# BrainA2-B-11Nov2014.net
KiCad netlist of a schematic drawn in EAGLE
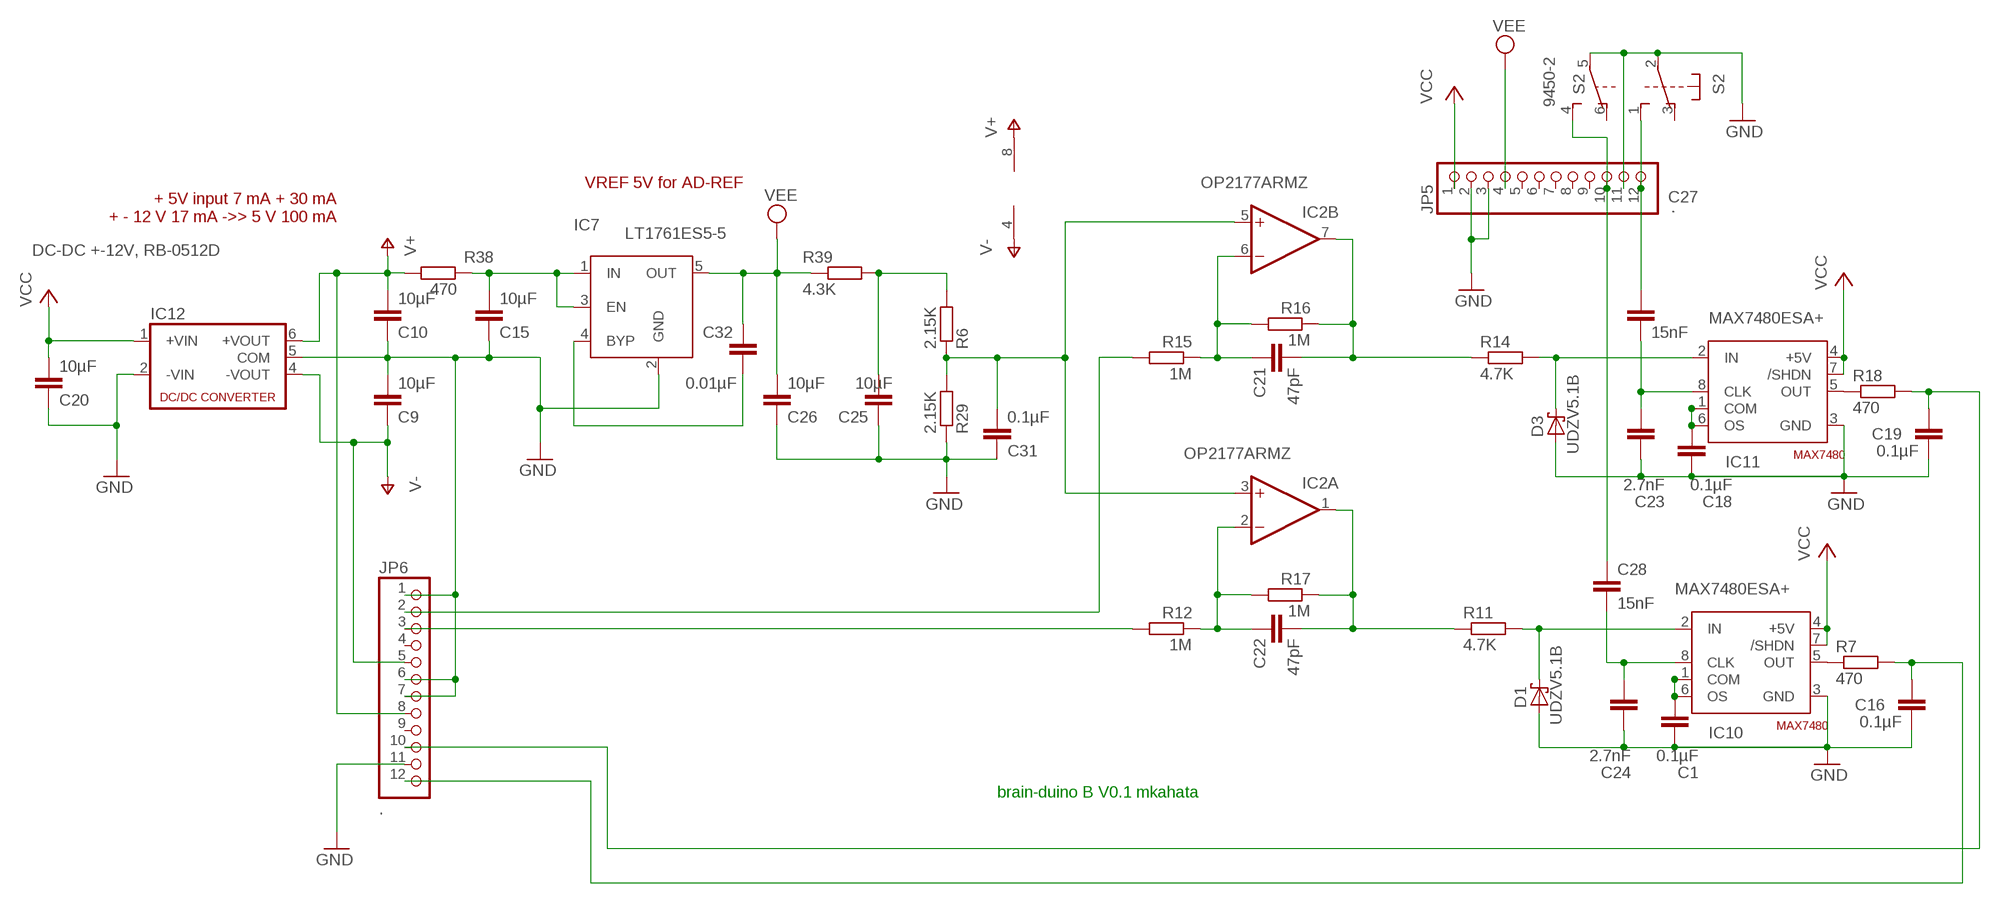
[diagram p0: schematic, sheet 1]

(export (version "E")
  (design (tool "Eeschema 10.0.6"))
  (components
    (comp (ref "C1")
      (value "0.1µF")
      (footprint "eagle-import:C0603")
      (libsource (lib "eagle-import") (part "C-EUC0603"))
    )
    (comp (ref "C9")
      (value "10µF")
      (footprint "eagle-import:C0603")
      (libsource (lib "eagle-import") (part "C-EUC0603"))
    )
    (comp (ref "C10")
      (value "10µF")
      (footprint "eagle-import:C0603")
      (libsource (lib "eagle-import") (part "C-EUC0603"))
    )
    (comp (ref "C15")
      (value "10µF")
      (footprint "eagle-import:C0603")
      (libsource (lib "eagle-import") (part "C-EUC0603"))
    )
    (comp (ref "C16")
      (value "0.1µF")
      (footprint "eagle-import:C0603")
      (libsource (lib "eagle-import") (part "C-EUC0603"))
    )
    (comp (ref "C18")
      (value "0.1µF")
      (footprint "eagle-import:C0603")
      (libsource (lib "eagle-import") (part "C-EUC0603"))
    )
    (comp (ref "C19")
      (value "0.1µF")
      (footprint "eagle-import:C0603")
      (libsource (lib "eagle-import") (part "C-EUC0603"))
    )
    (comp (ref "C20")
      (value "10µF")
      (footprint "eagle-import:C0603")
      (libsource (lib "eagle-import") (part "C-EUC0603"))
    )
    (comp (ref "C21")
      (value "47pF")
      (footprint "eagle-import:C0603")
      (libsource (lib "eagle-import") (part "C-EUC0603"))
    )
    (comp (ref "C22")
      (value "47pF")
      (footprint "eagle-import:C0603")
      (libsource (lib "eagle-import") (part "C-EUC0603"))
    )
    (comp (ref "C23")
      (value "2.7nF")
      (footprint "eagle-import:C0603")
      (libsource (lib "eagle-import") (part "C-EUC0603"))
    )
    (comp (ref "C24")
      (value "2.7nF")
      (footprint "eagle-import:C0603")
      (libsource (lib "eagle-import") (part "C-EUC0603"))
    )
    (comp (ref "C25")
      (value "10µF")
      (footprint "eagle-import:C0603")
      (libsource (lib "eagle-import") (part "C-EUC0603"))
    )
    (comp (ref "C26")
      (value "10µF")
      (footprint "eagle-import:C0603")
      (libsource (lib "eagle-import") (part "C-EUC0603"))
    )
    (comp (ref "C27")
      (value "15nF")
      (footprint "eagle-import:C0603")
      (libsource (lib "eagle-import") (part "C-EUC0603"))
    )
    (comp (ref "C28")
      (value "15nF")
      (footprint "eagle-import:C0603")
      (libsource (lib "eagle-import") (part "C-EUC0603"))
    )
    (comp (ref "C31")
      (value "0.1µF")
      (footprint "eagle-import:C0603")
      (libsource (lib "eagle-import") (part "C-EUC0603"))
    )
    (comp (ref "C32")
      (value "0.01µF")
      (footprint "eagle-import:C0603")
      (libsource (lib "eagle-import") (part "C-EUC0603"))
    )
    (comp (ref "D1")
      (value "UDZV5.1B")
      (footprint "eagle-import:SOD323_ST")
      (libsource (lib "eagle-import") (part "BAT60J"))
    )
    (comp (ref "D3")
      (value "UDZV5.1B")
      (footprint "eagle-import:SOD323_ST")
      (libsource (lib "eagle-import") (part "BAT60J"))
    )
    (comp (ref "IC2")
      (value "OP2177ARMZ")
      (footprint "eagle-import:MSOP08")
      (libsource (lib "eagle-import") (part "OP1277RM"))
    )
    (comp (ref "IC7")
      (value "LT1761ES5-5")
      (footprint "eagle-import:SOT23-5")
      (libsource (lib "eagle-import") (part "MIC5219XX"))
    )
    (comp (ref "IC10")
      (value "MAX7480ESA+")
      (footprint "eagle-import:MAX7480")
      (libsource (lib "eagle-import") (part "MAX7480"))
    )
    (comp (ref "IC11")
      (value "MAX7480ESA+")
      (footprint "eagle-import:MAX7480")
      (libsource (lib "eagle-import") (part "MAX7480"))
    )
    (comp (ref "IC12")
      (value "DC-DC +-12V, RB-0512D")
      (footprint "eagle-import:RB-0515D")
      (libsource (lib "eagle-import") (part "RB-0515D"))
    )
    (comp (ref "JP5")
      (value ".")
      (footprint "eagle-import:1X12")
      (libsource (lib "eagle-import") (part "PINHD-1X12"))
    )
    (comp (ref "JP6")
      (value ".")
      (footprint "eagle-import:1X12")
      (libsource (lib "eagle-import") (part "PINHD-1X12"))
    )
    (comp (ref "R6")
      (value "2.15K")
      (footprint "eagle-import:R0603")
      (libsource (lib "eagle-import") (part "R-EU_R0603"))
    )
    (comp (ref "R7")
      (value "470")
      (footprint "eagle-import:R0603")
      (libsource (lib "eagle-import") (part "R-EU_R0603"))
    )
    (comp (ref "R11")
      (value "4.7K")
      (footprint "eagle-import:R0603")
      (libsource (lib "eagle-import") (part "R-EU_R0603"))
    )
    (comp (ref "R12")
      (value "1M")
      (footprint "eagle-import:R0603")
      (libsource (lib "eagle-import") (part "R-EU_R0603"))
    )
    (comp (ref "R14")
      (value "4.7K")
      (footprint "eagle-import:R0603")
      (libsource (lib "eagle-import") (part "R-EU_R0603"))
    )
    (comp (ref "R15")
      (value "1M")
      (footprint "eagle-import:R0603")
      (libsource (lib "eagle-import") (part "R-EU_R0603"))
    )
    (comp (ref "R16")
      (value "1M")
      (footprint "eagle-import:R0603")
      (libsource (lib "eagle-import") (part "R-EU_R0603"))
    )
    (comp (ref "R17")
      (value "1M")
      (footprint "eagle-import:R0603")
      (libsource (lib "eagle-import") (part "R-EU_R0603"))
    )
    (comp (ref "R18")
      (value "470")
      (footprint "eagle-import:R0603")
      (libsource (lib "eagle-import") (part "R-EU_R0603"))
    )
    (comp (ref "R29")
      (value "2.15K")
      (footprint "eagle-import:R0603")
      (libsource (lib "eagle-import") (part "R-EU_R0603"))
    )
    (comp (ref "R38")
      (value "470")
      (footprint "eagle-import:R0603")
      (libsource (lib "eagle-import") (part "R-EU_R0603"))
    )
    (comp (ref "R39")
      (value "4.3K")
      (footprint "eagle-import:R0603")
      (libsource (lib "eagle-import") (part "R-EU_R0603"))
    )
    (comp (ref "S2")
      (value "9450-2")
      (footprint "eagle-import:9450-2")
      (libsource (lib "eagle-import") (part "9450-2"))
    )
  )
  (nets
    (net (code "1") (name "GND") (class "Default")
      (node (ref "C1") (pin "1") (pinfunction "1_1") (pintype "passive"))
      (node (ref "C10") (pin "1") (pinfunction "1_1") (pintype "passive"))
      (node (ref "C15") (pin "1") (pinfunction "1_1") (pintype "passive"))
      (node (ref "C16") (pin "1") (pinfunction "1_1") (pintype "passive"))
      (node (ref "C18") (pin "1") (pinfunction "1_1") (pintype "passive"))
      (node (ref "C19") (pin "1") (pinfunction "1_1") (pintype "passive"))
      (node (ref "C20") (pin "1") (pinfunction "1_1") (pintype "passive"))
      (node (ref "C23") (pin "1") (pinfunction "1_1") (pintype "passive"))
      (node (ref "C24") (pin "1") (pinfunction "1_1") (pintype "passive"))
      (node (ref "C25") (pin "1") (pinfunction "1_1") (pintype "passive"))
      (node (ref "C26") (pin "1") (pinfunction "1_1") (pintype "passive"))
      (node (ref "C31") (pin "1") (pinfunction "1_1") (pintype "passive"))
      (node (ref "C9") (pin "2") (pinfunction "2_2") (pintype "passive"))
      (node (ref "D1") (pin "A") (pinfunction "A_A") (pintype "passive"))
      (node (ref "D3") (pin "A") (pinfunction "A_A") (pintype "passive"))
      (node (ref "IC10") (pin "3") (pinfunction "GND_3") (pintype "power_in"))
      (node (ref "IC11") (pin "3") (pinfunction "GND_3") (pintype "power_in"))
      (node (ref "IC12") (pin "2") (pinfunction "-VIN_2") (pintype "passive"))
      (node (ref "IC12") (pin "5") (pinfunction "COM_5") (pintype "passive"))
      (node (ref "IC7") (pin "2") (pinfunction "GND_2") (pintype "power_in"))
      (node (ref "JP5") (pin "11") (pinfunction "11_11") (pintype "passive"))
      (node (ref "JP5") (pin "2") (pinfunction "2_2") (pintype "passive"))
      (node (ref "JP5") (pin "3") (pinfunction "3_3") (pintype "passive"))
      (node (ref "JP6") (pin "1") (pinfunction "1_1") (pintype "passive"))
      (node (ref "JP6") (pin "11") (pinfunction "11_11") (pintype "passive"))
      (node (ref "JP6") (pin "6") (pinfunction "6_6") (pintype "passive"))
      (node (ref "JP6") (pin "7") (pinfunction "7_7") (pintype "passive"))
      (node (ref "R29") (pin "1") (pinfunction "1_1") (pintype "passive"))
      (node (ref "S2") (pin "2") (pinfunction "P_2") (pintype "passive"))
      (node (ref "S2") (pin "5") (pinfunction "P_5") (pintype "passive"))
    )
    (net (code "2") (name "Net-(C16-Pad2)") (class "Default")
      (node (ref "C16") (pin "2") (pinfunction "2_2") (pintype "passive"))
      (node (ref "JP6") (pin "12") (pinfunction "12_12") (pintype "passive"))
      (node (ref "R7") (pin "2") (pinfunction "2_2") (pintype "passive"))
    )
    (net (code "3") (name "Net-(C19-Pad2)") (class "Default")
      (node (ref "C19") (pin "2") (pinfunction "2_2") (pintype "passive"))
      (node (ref "JP6") (pin "10") (pinfunction "10_10") (pintype "passive"))
      (node (ref "R18") (pin "2") (pinfunction "2_2") (pintype "passive"))
    )
    (net (code "4") (name "Net-(C25-Pad2)") (class "Default")
      (node (ref "C25") (pin "2") (pinfunction "2_2") (pintype "passive"))
      (node (ref "R39") (pin "2") (pinfunction "2_2") (pintype "passive"))
      (node (ref "R6") (pin "2") (pinfunction "2_2") (pintype "passive"))
    )
    (net (code "5") (name "Net-(IC2A-+IN)") (class "Default")
      (node (ref "C31") (pin "2") (pinfunction "2_2") (pintype "passive"))
      (node (ref "IC2") (pin "3") (pinfunction "+IN_3") (pintype "input"))
      (node (ref "IC2") (pin "5") (pinfunction "+IN_5") (pintype "input"))
      (node (ref "R29") (pin "2") (pinfunction "2_2") (pintype "passive"))
      (node (ref "R6") (pin "1") (pinfunction "1_1") (pintype "passive"))
    )
    (net (code "6") (name "Net-(IC2A--IN)") (class "Default")
      (node (ref "C22") (pin "1") (pinfunction "1_1") (pintype "passive"))
      (node (ref "IC2") (pin "2") (pinfunction "-IN_2") (pintype "input"))
      (node (ref "R12") (pin "1") (pinfunction "1_1") (pintype "passive"))
      (node (ref "R17") (pin "2") (pinfunction "2_2") (pintype "passive"))
    )
    (net (code "7") (name "Net-(IC2A-OUT)") (class "Default")
      (node (ref "C22") (pin "2") (pinfunction "2_2") (pintype "passive"))
      (node (ref "IC2") (pin "1") (pinfunction "OUT_1") (pintype "output"))
      (node (ref "R11") (pin "1") (pinfunction "1_1") (pintype "passive"))
      (node (ref "R17") (pin "1") (pinfunction "1_1") (pintype "passive"))
    )
    (net (code "8") (name "Net-(IC2B--IN)") (class "Default")
      (node (ref "C21") (pin "1") (pinfunction "1_1") (pintype "passive"))
      (node (ref "IC2") (pin "6") (pinfunction "-IN_6") (pintype "input"))
      (node (ref "R15") (pin "1") (pinfunction "1_1") (pintype "passive"))
      (node (ref "R16") (pin "2") (pinfunction "2_2") (pintype "passive"))
    )
    (net (code "9") (name "Net-(IC2B-OUT)") (class "Default")
      (node (ref "C21") (pin "2") (pinfunction "2_2") (pintype "passive"))
      (node (ref "IC2") (pin "7") (pinfunction "OUT_7") (pintype "output"))
      (node (ref "R14") (pin "1") (pinfunction "1_1") (pintype "passive"))
      (node (ref "R16") (pin "1") (pinfunction "1_1") (pintype "passive"))
    )
    (net (code "10") (name "Net-(IC7-BYP)") (class "Default")
      (node (ref "C32") (pin "1") (pinfunction "1_1") (pintype "passive"))
      (node (ref "IC7") (pin "4") (pinfunction "BYP_4") (pintype "passive"))
    )
    (net (code "11") (name "Net-(IC7-EN)") (class "Default")
      (node (ref "C15") (pin "2") (pinfunction "2_2") (pintype "passive"))
      (node (ref "IC7") (pin "1") (pinfunction "IN_1") (pintype "input"))
      (node (ref "IC7") (pin "3") (pinfunction "EN_3") (pintype "input"))
      (node (ref "R38") (pin "2") (pinfunction "2_2") (pintype "passive"))
    )
    (net (code "12") (name "Net-(IC10-CLK)") (class "Default")
      (node (ref "C24") (pin "2") (pinfunction "2_2") (pintype "passive"))
      (node (ref "C28") (pin "2") (pinfunction "2_2") (pintype "passive"))
      (node (ref "IC10") (pin "8") (pinfunction "CLK_8") (pintype "input"))
    )
    (net (code "13") (name "Net-(IC10-COM)") (class "Default")
      (node (ref "C1") (pin "2") (pinfunction "2_2") (pintype "passive"))
      (node (ref "IC10") (pin "1") (pinfunction "COM_1") (pintype "input"))
      (node (ref "IC10") (pin "6") (pinfunction "OS_6") (pintype "passive"))
    )
    (net (code "14") (name "Net-(IC10-IN)") (class "Default")
      (node (ref "D1") (pin "C") (pinfunction "C_C") (pintype "passive"))
      (node (ref "IC10") (pin "2") (pinfunction "IN_2") (pintype "input"))
      (node (ref "R11") (pin "2") (pinfunction "2_2") (pintype "passive"))
    )
    (net (code "15") (name "Net-(IC10-OUT)") (class "Default")
      (node (ref "IC10") (pin "5") (pinfunction "OUT_5") (pintype "input"))
      (node (ref "R7") (pin "1") (pinfunction "1_1") (pintype "passive"))
    )
    (net (code "16") (name "Net-(IC11-CLK)") (class "Default")
      (node (ref "C23") (pin "2") (pinfunction "2_2") (pintype "passive"))
      (node (ref "C27") (pin "2") (pinfunction "2_2") (pintype "passive"))
      (node (ref "IC11") (pin "8") (pinfunction "CLK_8") (pintype "input"))
    )
    (net (code "17") (name "Net-(IC11-COM)") (class "Default")
      (node (ref "C18") (pin "2") (pinfunction "2_2") (pintype "passive"))
      (node (ref "IC11") (pin "1") (pinfunction "COM_1") (pintype "input"))
      (node (ref "IC11") (pin "6") (pinfunction "OS_6") (pintype "passive"))
    )
    (net (code "18") (name "Net-(IC11-IN)") (class "Default")
      (node (ref "D3") (pin "C") (pinfunction "C_C") (pintype "passive"))
      (node (ref "IC11") (pin "2") (pinfunction "IN_2") (pintype "input"))
      (node (ref "R14") (pin "2") (pinfunction "2_2") (pintype "passive"))
    )
    (net (code "19") (name "Net-(IC11-OUT)") (class "Default")
      (node (ref "IC11") (pin "5") (pinfunction "OUT_5") (pintype "input"))
      (node (ref "R18") (pin "1") (pinfunction "1_1") (pintype "passive"))
    )
    (net (code "20") (name "Net-(JP6-Pad2)") (class "Default")
      (node (ref "JP6") (pin "2") (pinfunction "2_2") (pintype "passive"))
      (node (ref "R15") (pin "2") (pinfunction "2_2") (pintype "passive"))
    )
    (net (code "21") (name "Net-(JP6-Pad3)") (class "Default")
      (node (ref "JP6") (pin "3") (pinfunction "3_3") (pintype "passive"))
      (node (ref "R12") (pin "2") (pinfunction "2_2") (pintype "passive"))
    )
    (net (code "22") (name "Net-(S2A-S)") (class "Default")
      (node (ref "C27") (pin "1") (pinfunction "1_1") (pintype "passive"))
      (node (ref "JP5") (pin "12") (pinfunction "12_12") (pintype "passive"))
      (node (ref "S2") (pin "1") (pinfunction "S_1") (pintype "passive"))
    )
    (net (code "23") (name "Net-(S2B-S)") (class "Default")
      (node (ref "C28") (pin "1") (pinfunction "1_1") (pintype "passive"))
      (node (ref "JP5") (pin "10") (pinfunction "10_10") (pintype "passive"))
      (node (ref "S2") (pin "4") (pinfunction "S_4") (pintype "passive"))
    )
    (net (code "24") (name "V+") (class "Default")
      (node (ref "C10") (pin "2") (pinfunction "2_2") (pintype "passive"))
      (node (ref "IC12") (pin "6") (pinfunction "+VOUT_6") (pintype "passive"))
      (node (ref "IC2") (pin "8") (pinfunction "V+_8") (pintype "power_in"))
      (node (ref "JP6") (pin "8") (pinfunction "8_8") (pintype "passive"))
      (node (ref "R38") (pin "1") (pinfunction "1_1") (pintype "passive"))
    )
    (net (code "25") (name "V-") (class "Default")
      (node (ref "C9") (pin "1") (pinfunction "1_1") (pintype "passive"))
      (node (ref "IC12") (pin "4") (pinfunction "-VOUT_4") (pintype "passive"))
      (node (ref "IC2") (pin "4") (pinfunction "V-_4") (pintype "power_in"))
      (node (ref "JP6") (pin "5") (pinfunction "5_5") (pintype "passive"))
    )
    (net (code "26") (name "VCC") (class "Default")
      (node (ref "C20") (pin "2") (pinfunction "2_2") (pintype "passive"))
      (node (ref "IC10") (pin "4") (pinfunction "+5V_4") (pintype "power_in"))
      (node (ref "IC10") (pin "7") (pinfunction "/SHDN_7") (pintype "input"))
      (node (ref "IC11") (pin "4") (pinfunction "+5V_4") (pintype "power_in"))
      (node (ref "IC11") (pin "7") (pinfunction "/SHDN_7") (pintype "input"))
      (node (ref "IC12") (pin "1") (pinfunction "+VIN_1") (pintype "passive"))
      (node (ref "JP5") (pin "1") (pinfunction "1_1") (pintype "passive"))
    )
    (net (code "27") (name "VEE") (class "Default")
      (node (ref "C26") (pin "2") (pinfunction "2_2") (pintype "passive"))
      (node (ref "C32") (pin "2") (pinfunction "2_2") (pintype "passive"))
      (node (ref "IC7") (pin "5") (pinfunction "OUT_5") (pintype "output"))
      (node (ref "JP5") (pin "4") (pinfunction "4_4") (pintype "passive"))
      (node (ref "R39") (pin "1") (pinfunction "1_1") (pintype "passive"))
    )
    (net (code "28") (name "unconnected-(JP5-Pad5)") (class "Default")
      (node (ref "JP5") (pin "5") (pinfunction "5_5") (pintype "passive"))
    )
    (net (code "29") (name "unconnected-(JP5-Pad6)") (class "Default")
      (node (ref "JP5") (pin "6") (pinfunction "6_6") (pintype "passive"))
    )
    (net (code "30") (name "unconnected-(JP5-Pad7)") (class "Default")
      (node (ref "JP5") (pin "7") (pinfunction "7_7") (pintype "passive"))
    )
    (net (code "31") (name "unconnected-(JP5-Pad8)") (class "Default")
      (node (ref "JP5") (pin "8") (pinfunction "8_8") (pintype "passive"))
    )
    (net (code "32") (name "unconnected-(JP5-Pad9)") (class "Default")
      (node (ref "JP5") (pin "9") (pinfunction "9_9") (pintype "passive"))
    )
    (net (code "33") (name "unconnected-(JP6-Pad4)") (class "Default")
      (node (ref "JP6") (pin "4") (pinfunction "4_4") (pintype "passive"))
    )
    (net (code "34") (name "unconnected-(JP6-Pad9)") (class "Default")
      (node (ref "JP6") (pin "9") (pinfunction "9_9") (pintype "passive"))
    )
    (net (code "35") (name "unconnected-(S2A-O-Pad3)") (class "Default")
      (node (ref "S2") (pin "3") (pinfunction "O_3") (pintype "passive"))
    )
    (net (code "36") (name "unconnected-(S2B-O-Pad6)") (class "Default")
      (node (ref "S2") (pin "6") (pinfunction "O_6") (pintype "passive"))
    )
  )
)
